# ADS1015_shield.net
KiCad netlist of a schematic drawn in EAGLE
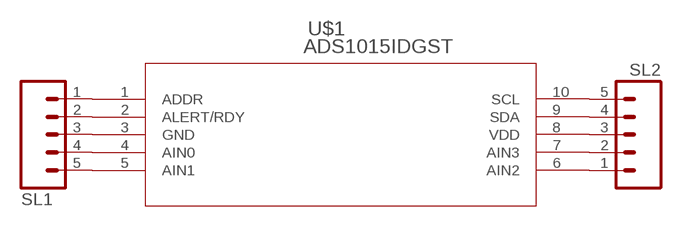
[diagram p0: schematic, sheet 1]

(export (version "E")
  (design (tool "Eeschema 10.0.6"))
  (components
    (comp (ref "SL1")
      (value "M05")
      (footprint "eagle-import:05P")
      (libsource (lib "eagle-import") (part "M05"))
    )
    (comp (ref "SL2")
      (value "M05")
      (footprint "eagle-import:05P")
      (libsource (lib "eagle-import") (part "M05"))
    )
    (comp (ref "U$1")
      (value "ADS1015IDGST")
      (footprint "eagle-import:DGS10")
      (fields
        (field (name "RSPARTNUMBER") "7094550")
        (field (name "COPYRIGHT") "Copyright C 2015 Accelerated Designs. All rights reserved")
      )
      (libsource (lib "eagle-import") (part "ADS1015IDGST"))
    )
  )
  (nets
    (net (code "1") (name "Net-(U$1-ADDR)") (class "Default")
      (node (ref "SL1") (pin "1") (pinfunction "1_1") (pintype "passive"))
      (node (ref "U$1") (pin "1") (pinfunction "ADDR_1") (pintype "input"))
    )
    (net (code "2") (name "Net-(U$1-AIN0)") (class "Default")
      (node (ref "SL1") (pin "4") (pinfunction "4_4") (pintype "passive"))
      (node (ref "U$1") (pin "4") (pinfunction "AIN0_4") (pintype "input"))
    )
    (net (code "3") (name "Net-(U$1-AIN1)") (class "Default")
      (node (ref "SL1") (pin "5") (pinfunction "5_5") (pintype "passive"))
      (node (ref "U$1") (pin "5") (pinfunction "AIN1_5") (pintype "input"))
    )
    (net (code "4") (name "Net-(U$1-AIN2)") (class "Default")
      (node (ref "SL2") (pin "1") (pinfunction "1_1") (pintype "passive"))
      (node (ref "U$1") (pin "6") (pinfunction "AIN2_6") (pintype "input"))
    )
    (net (code "5") (name "Net-(U$1-AIN3)") (class "Default")
      (node (ref "SL2") (pin "2") (pinfunction "2_2") (pintype "passive"))
      (node (ref "U$1") (pin "7") (pinfunction "AIN3_7") (pintype "input"))
    )
    (net (code "6") (name "Net-(U$1-ALERT{slash}RDY)") (class "Default")
      (node (ref "SL1") (pin "2") (pinfunction "2_2") (pintype "passive"))
      (node (ref "U$1") (pin "2") (pinfunction "ALERT/RDY_2") (pintype "output"))
    )
    (net (code "7") (name "Net-(U$1-GND)") (class "Default")
      (node (ref "SL1") (pin "3") (pinfunction "3_3") (pintype "passive"))
      (node (ref "U$1") (pin "3") (pinfunction "GND_3") (pintype "power_in"))
    )
    (net (code "8") (name "Net-(U$1-SCL)") (class "Default")
      (node (ref "SL2") (pin "5") (pinfunction "5_5") (pintype "passive"))
      (node (ref "U$1") (pin "10") (pinfunction "SCL_10") (pintype "input"))
    )
    (net (code "9") (name "Net-(U$1-SDA)") (class "Default")
      (node (ref "SL2") (pin "4") (pinfunction "4_4") (pintype "passive"))
      (node (ref "U$1") (pin "9") (pinfunction "SDA_9") (pintype "bidirectional"))
    )
    (net (code "10") (name "Net-(U$1-VDD)") (class "Default")
      (node (ref "SL2") (pin "3") (pinfunction "3_3") (pintype "passive"))
      (node (ref "U$1") (pin "8") (pinfunction "VDD_8") (pintype "power_in"))
    )
  )
)
